# Housing_Interconnect.net
KiCad netlist of a schematic drawn in Altium Designer
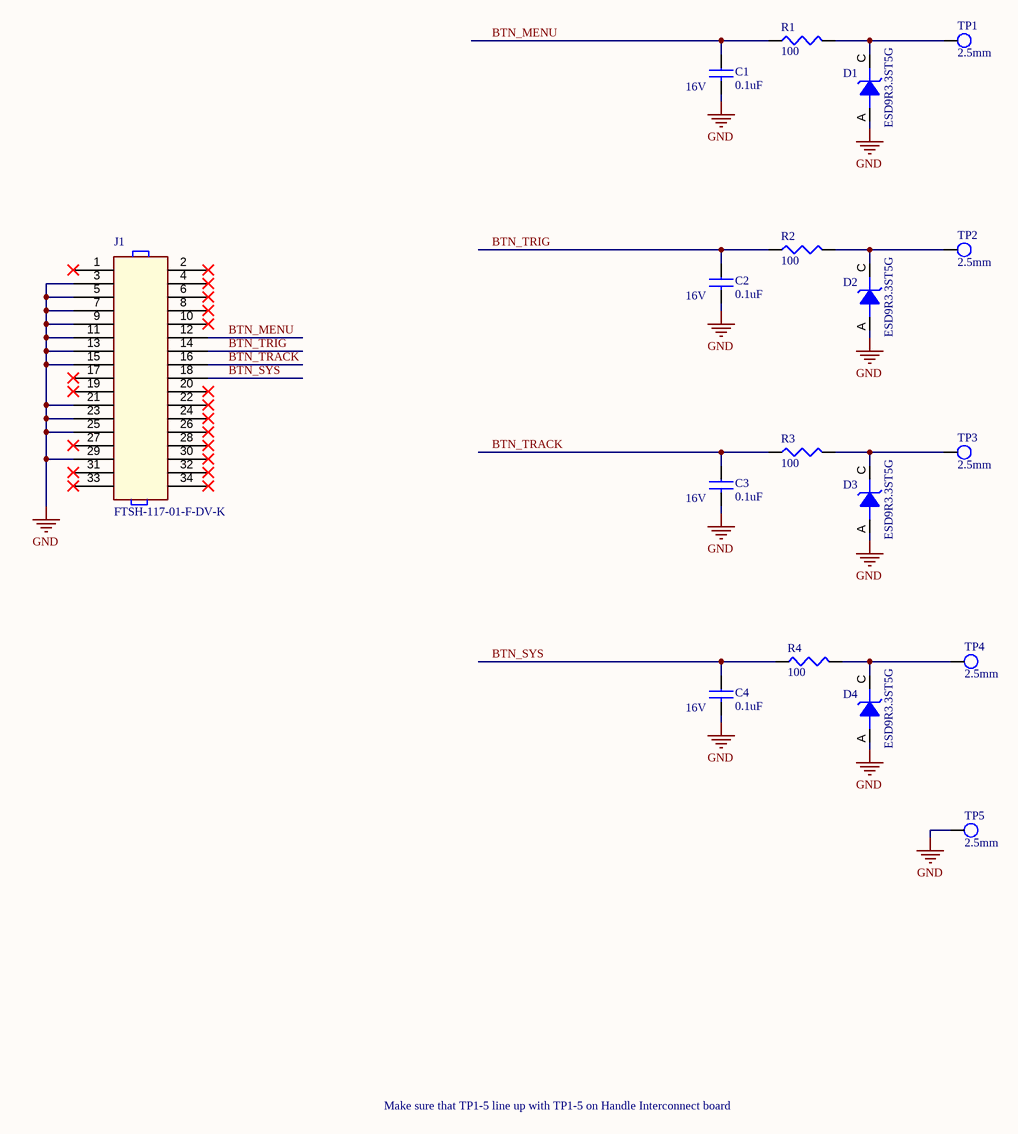
[diagram p0: Housing_Interconnect.SchDoc]

(export (version "E")
  (design (tool "Eeschema 10.0.6"))
  (components
    (comp (ref "C1")
      (value "0.1uF")
      (footprint "0402-IPCsm_55")
      (description "CAP CER .1UF 16V X7R 0402")
      (fields (field (name "VOLTAGE") "16V") (field (name "MFG") "MURATA") (field (name "TOLERANCE") "10%"))
      (libsource (lib "SynapseLibrary") (part "CAP"))
    )
    (comp (ref "C2")
      (value "0.1uF")
      (footprint "0402-IPCsm_55")
      (description "CAP CER .1UF 16V X7R 0402")
      (fields (field (name "VOLTAGE") "16V") (field (name "MFG") "MURATA") (field (name "TOLERANCE") "10%"))
      (libsource (lib "SynapseLibrary") (part "CAP"))
    )
    (comp (ref "C3")
      (value "0.1uF")
      (footprint "0402-IPCsm_55")
      (description "CAP CER .1UF 16V X7R 0402")
      (fields (field (name "VOLTAGE") "16V") (field (name "MFG") "MURATA") (field (name "TOLERANCE") "10%"))
      (libsource (lib "SynapseLibrary") (part "CAP"))
    )
    (comp (ref "C4")
      (value "0.1uF")
      (footprint "0402-IPCsm_55")
      (description "CAP CER .1UF 16V X7R 0402")
      (fields (field (name "VOLTAGE") "16V") (field (name "MFG") "MURATA") (field (name "TOLERANCE") "10%"))
      (libsource (lib "SynapseLibrary") (part "CAP"))
    )
    (comp (ref "D1")
      (value "ESD9R3.3ST5G")
      (footprint "sod923-40")
      (description "TVS DIODE 3.3VWM 7.8VC SOD923")
      (fields (field (name "MFG") "On Semiconductor") (field (name "VOLTAGE") "3.3V"))
      (libsource (lib "SynapseLibrary") (part "TVS_UNI"))
    )
    (comp (ref "D2")
      (value "ESD9R3.3ST5G")
      (footprint "sod923-40")
      (description "TVS DIODE 3.3VWM 7.8VC SOD923")
      (fields (field (name "MFG") "On Semiconductor") (field (name "VOLTAGE") "3.3V"))
      (libsource (lib "SynapseLibrary") (part "TVS_UNI"))
    )
    (comp (ref "D3")
      (value "ESD9R3.3ST5G")
      (footprint "sod923-40")
      (description "TVS DIODE 3.3VWM 7.8VC SOD923")
      (fields (field (name "MFG") "On Semiconductor") (field (name "VOLTAGE") "3.3V"))
      (libsource (lib "SynapseLibrary") (part "TVS_UNI"))
    )
    (comp (ref "D4")
      (value "ESD9R3.3ST5G")
      (footprint "sod923-40")
      (description "TVS DIODE 3.3VWM 7.8VC SOD923")
      (fields (field (name "MFG") "On Semiconductor") (field (name "VOLTAGE") "3.3V"))
      (libsource (lib "SynapseLibrary") (part "TVS_UNI"))
    )
    (comp (ref "J1")
      (value "FTSH-117-01-F-DV-K")
      (footprint "FTSH-117-01-XXX-DV-K")
      (description "34 Positions Header, Shrouded Connector 0.050\" (1.27mm) Surface Mount Gold")
      (fields (field (name "MFG") "Samtec"))
      (libsource (lib "SynapseLibrary") (part "HEADER 17X2"))
    )
    (comp (ref "R1")
      (value "100")
      (footprint "0402-IPCsm_40")
      (description "RES 100 OHM 5% 0402 SMD")
      (fields (field (name "TOLERANCE") "5.00%") (field (name "MFG") "ROHM"))
      (libsource (lib "SynapseLibrary") (part "RES"))
    )
    (comp (ref "R2")
      (value "100")
      (footprint "0402-IPCsm_40")
      (description "RES 100 OHM 5% 0402 SMD")
      (fields (field (name "TOLERANCE") "5.00%") (field (name "MFG") "ROHM"))
      (libsource (lib "SynapseLibrary") (part "RES"))
    )
    (comp (ref "R3")
      (value "100")
      (footprint "0402-IPCsm_40")
      (description "RES 100 OHM 5% 0402 SMD")
      (fields (field (name "TOLERANCE") "5.00%") (field (name "MFG") "ROHM"))
      (libsource (lib "SynapseLibrary") (part "RES"))
    )
    (comp (ref "R4")
      (value "100")
      (footprint "0402-IPCsm_40")
      (description "RES 100 OHM 5% 0402 SMD")
      (fields (field (name "TOLERANCE") "5.00%") (field (name "MFG") "ROHM"))
      (libsource (lib "SynapseLibrary") (part "RES"))
    )
    (comp (ref "TP1")
      (value "2.5mm")
      (footprint "TPC250SMT")
      (description "TEST POINT, SMT, 2.50mm")
      (fields (field (name "MFG") "NA"))
      (libsource (lib "SynapseLibrary") (part "tp_smt"))
    )
    (comp (ref "TP2")
      (value "2.5mm")
      (footprint "TPC250SMT")
      (description "TEST POINT, SMT, 2.50mm")
      (fields (field (name "MFG") "NA"))
      (libsource (lib "SynapseLibrary") (part "tp_smt"))
    )
    (comp (ref "TP3")
      (value "2.5mm")
      (footprint "TPC250SMT")
      (description "TEST POINT, SMT, 2.50mm")
      (fields (field (name "MFG") "NA"))
      (libsource (lib "SynapseLibrary") (part "tp_smt"))
    )
    (comp (ref "TP4")
      (value "2.5mm")
      (footprint "TPC250SMT")
      (description "TEST POINT, SMT, 2.50mm")
      (fields (field (name "MFG") "NA"))
      (libsource (lib "SynapseLibrary") (part "tp_smt"))
    )
    (comp (ref "TP5")
      (value "2.5mm")
      (footprint "TPC250SMT")
      (description "TEST POINT, SMT, 2.50mm")
      (fields (field (name "MFG") "NA"))
      (libsource (lib "SynapseLibrary") (part "tp_smt"))
    )
  )
  (nets
    (net (code "1") (name "/BTN_MENU") (class "Default")
      (node (ref "C1") (pin "1") (pinfunction "1_1") (pintype "passive"))
      (node (ref "J1") (pin "12") (pinfunction "12_12") (pintype "passive"))
      (node (ref "R1") (pin "1") (pinfunction "1_1") (pintype "passive"))
    )
    (net (code "2") (name "/BTN_SYS") (class "Default")
      (node (ref "C4") (pin "1") (pinfunction "1_1") (pintype "passive"))
      (node (ref "J1") (pin "18") (pinfunction "18_18") (pintype "passive"))
      (node (ref "R4") (pin "1") (pinfunction "1_1") (pintype "passive"))
    )
    (net (code "3") (name "/BTN_TRACK") (class "Default")
      (node (ref "C3") (pin "1") (pinfunction "1_1") (pintype "passive"))
      (node (ref "J1") (pin "16") (pinfunction "16_16") (pintype "passive"))
      (node (ref "R3") (pin "1") (pinfunction "1_1") (pintype "passive"))
    )
    (net (code "4") (name "/BTN_TRIG") (class "Default")
      (node (ref "C2") (pin "1") (pinfunction "1_1") (pintype "passive"))
      (node (ref "J1") (pin "14") (pinfunction "14_14") (pintype "passive"))
      (node (ref "R2") (pin "1") (pinfunction "1_1") (pintype "passive"))
    )
    (net (code "5") (name "GND") (class "Default")
      (node (ref "C1") (pin "2") (pinfunction "2_2") (pintype "passive"))
      (node (ref "C2") (pin "2") (pinfunction "2_2") (pintype "passive"))
      (node (ref "C3") (pin "2") (pinfunction "2_2") (pintype "passive"))
      (node (ref "C4") (pin "2") (pinfunction "2_2") (pintype "passive"))
      (node (ref "D1") (pin "A") (pinfunction "A_A") (pintype "passive"))
      (node (ref "D2") (pin "A") (pinfunction "A_A") (pintype "passive"))
      (node (ref "D3") (pin "A") (pinfunction "A_A") (pintype "passive"))
      (node (ref "D4") (pin "A") (pinfunction "A_A") (pintype "passive"))
      (node (ref "J1") (pin "11") (pinfunction "11_11") (pintype "passive"))
      (node (ref "J1") (pin "13") (pinfunction "13_13") (pintype "passive"))
      (node (ref "J1") (pin "15") (pinfunction "15_15") (pintype "passive"))
      (node (ref "J1") (pin "21") (pinfunction "21_21") (pintype "passive"))
      (node (ref "J1") (pin "23") (pinfunction "23_23") (pintype "passive"))
      (node (ref "J1") (pin "25") (pinfunction "25_25") (pintype "passive"))
      (node (ref "J1") (pin "29") (pinfunction "29_29") (pintype "passive"))
      (node (ref "J1") (pin "3") (pinfunction "3_3") (pintype "passive"))
      (node (ref "J1") (pin "5") (pinfunction "5_5") (pintype "passive"))
      (node (ref "J1") (pin "7") (pinfunction "7_7") (pintype "passive"))
      (node (ref "J1") (pin "9") (pinfunction "9_9") (pintype "passive"))
      (node (ref "TP5") (pin "1") (pinfunction "TP_1") (pintype "passive"))
    )
    (net (code "6") (name "Net-(TP1-TP)") (class "Default")
      (node (ref "D1") (pin "C") (pinfunction "C_C") (pintype "passive"))
      (node (ref "R1") (pin "2") (pinfunction "2_2") (pintype "passive"))
      (node (ref "TP1") (pin "1") (pinfunction "TP_1") (pintype "passive"))
    )
    (net (code "7") (name "Net-(TP2-TP)") (class "Default")
      (node (ref "D2") (pin "C") (pinfunction "C_C") (pintype "passive"))
      (node (ref "R2") (pin "2") (pinfunction "2_2") (pintype "passive"))
      (node (ref "TP2") (pin "1") (pinfunction "TP_1") (pintype "passive"))
    )
    (net (code "8") (name "Net-(TP3-TP)") (class "Default")
      (node (ref "D3") (pin "C") (pinfunction "C_C") (pintype "passive"))
      (node (ref "R3") (pin "2") (pinfunction "2_2") (pintype "passive"))
      (node (ref "TP3") (pin "1") (pinfunction "TP_1") (pintype "passive"))
    )
    (net (code "9") (name "Net-(TP4-TP)") (class "Default")
      (node (ref "D4") (pin "C") (pinfunction "C_C") (pintype "passive"))
      (node (ref "R4") (pin "2") (pinfunction "2_2") (pintype "passive"))
      (node (ref "TP4") (pin "1") (pinfunction "TP_1") (pintype "passive"))
    )
    (net (code "10") (name "unconnected-(J1-Pad1)") (class "Default")
      (node (ref "J1") (pin "1") (pinfunction "1_1") (pintype "passive+no_connect"))
    )
    (net (code "11") (name "unconnected-(J1-Pad2)") (class "Default")
      (node (ref "J1") (pin "2") (pinfunction "2_2") (pintype "passive+no_connect"))
    )
    (net (code "12") (name "unconnected-(J1-Pad4)") (class "Default")
      (node (ref "J1") (pin "4") (pinfunction "4_4") (pintype "passive+no_connect"))
    )
    (net (code "13") (name "unconnected-(J1-Pad6)") (class "Default")
      (node (ref "J1") (pin "6") (pinfunction "6_6") (pintype "passive+no_connect"))
    )
    (net (code "14") (name "unconnected-(J1-Pad8)") (class "Default")
      (node (ref "J1") (pin "8") (pinfunction "8_8") (pintype "passive+no_connect"))
    )
    (net (code "15") (name "unconnected-(J1-Pad10)") (class "Default")
      (node (ref "J1") (pin "10") (pinfunction "10_10") (pintype "passive+no_connect"))
    )
    (net (code "16") (name "unconnected-(J1-Pad17)") (class "Default")
      (node (ref "J1") (pin "17") (pinfunction "17_17") (pintype "passive+no_connect"))
    )
    (net (code "17") (name "unconnected-(J1-Pad19)") (class "Default")
      (node (ref "J1") (pin "19") (pinfunction "19_19") (pintype "passive+no_connect"))
    )
    (net (code "18") (name "unconnected-(J1-Pad20)") (class "Default")
      (node (ref "J1") (pin "20") (pinfunction "20_20") (pintype "passive+no_connect"))
    )
    (net (code "19") (name "unconnected-(J1-Pad22)") (class "Default")
      (node (ref "J1") (pin "22") (pinfunction "22_22") (pintype "passive+no_connect"))
    )
    (net (code "20") (name "unconnected-(J1-Pad24)") (class "Default")
      (node (ref "J1") (pin "24") (pinfunction "24_24") (pintype "passive+no_connect"))
    )
    (net (code "21") (name "unconnected-(J1-Pad26)") (class "Default")
      (node (ref "J1") (pin "26") (pinfunction "26_26") (pintype "passive+no_connect"))
    )
    (net (code "22") (name "unconnected-(J1-Pad27)") (class "Default")
      (node (ref "J1") (pin "27") (pinfunction "27_27") (pintype "passive+no_connect"))
    )
    (net (code "23") (name "unconnected-(J1-Pad28)") (class "Default")
      (node (ref "J1") (pin "28") (pinfunction "28_28") (pintype "passive+no_connect"))
    )
    (net (code "24") (name "unconnected-(J1-Pad30)") (class "Default")
      (node (ref "J1") (pin "30") (pinfunction "30_30") (pintype "passive+no_connect"))
    )
    (net (code "25") (name "unconnected-(J1-Pad31)") (class "Default")
      (node (ref "J1") (pin "31") (pinfunction "31_31") (pintype "passive+no_connect"))
    )
    (net (code "26") (name "unconnected-(J1-Pad32)") (class "Default")
      (node (ref "J1") (pin "32") (pinfunction "32_32") (pintype "passive+no_connect"))
    )
    (net (code "27") (name "unconnected-(J1-Pad33)") (class "Default")
      (node (ref "J1") (pin "33") (pinfunction "33_33") (pintype "passive+no_connect"))
    )
    (net (code "28") (name "unconnected-(J1-Pad34)") (class "Default")
      (node (ref "J1") (pin "34") (pinfunction "34_34") (pintype "passive+no_connect"))
    )
  )
)
